# HPCC_Connector_B.net
KiCad netlist of a schematic drawn in Altium Designer
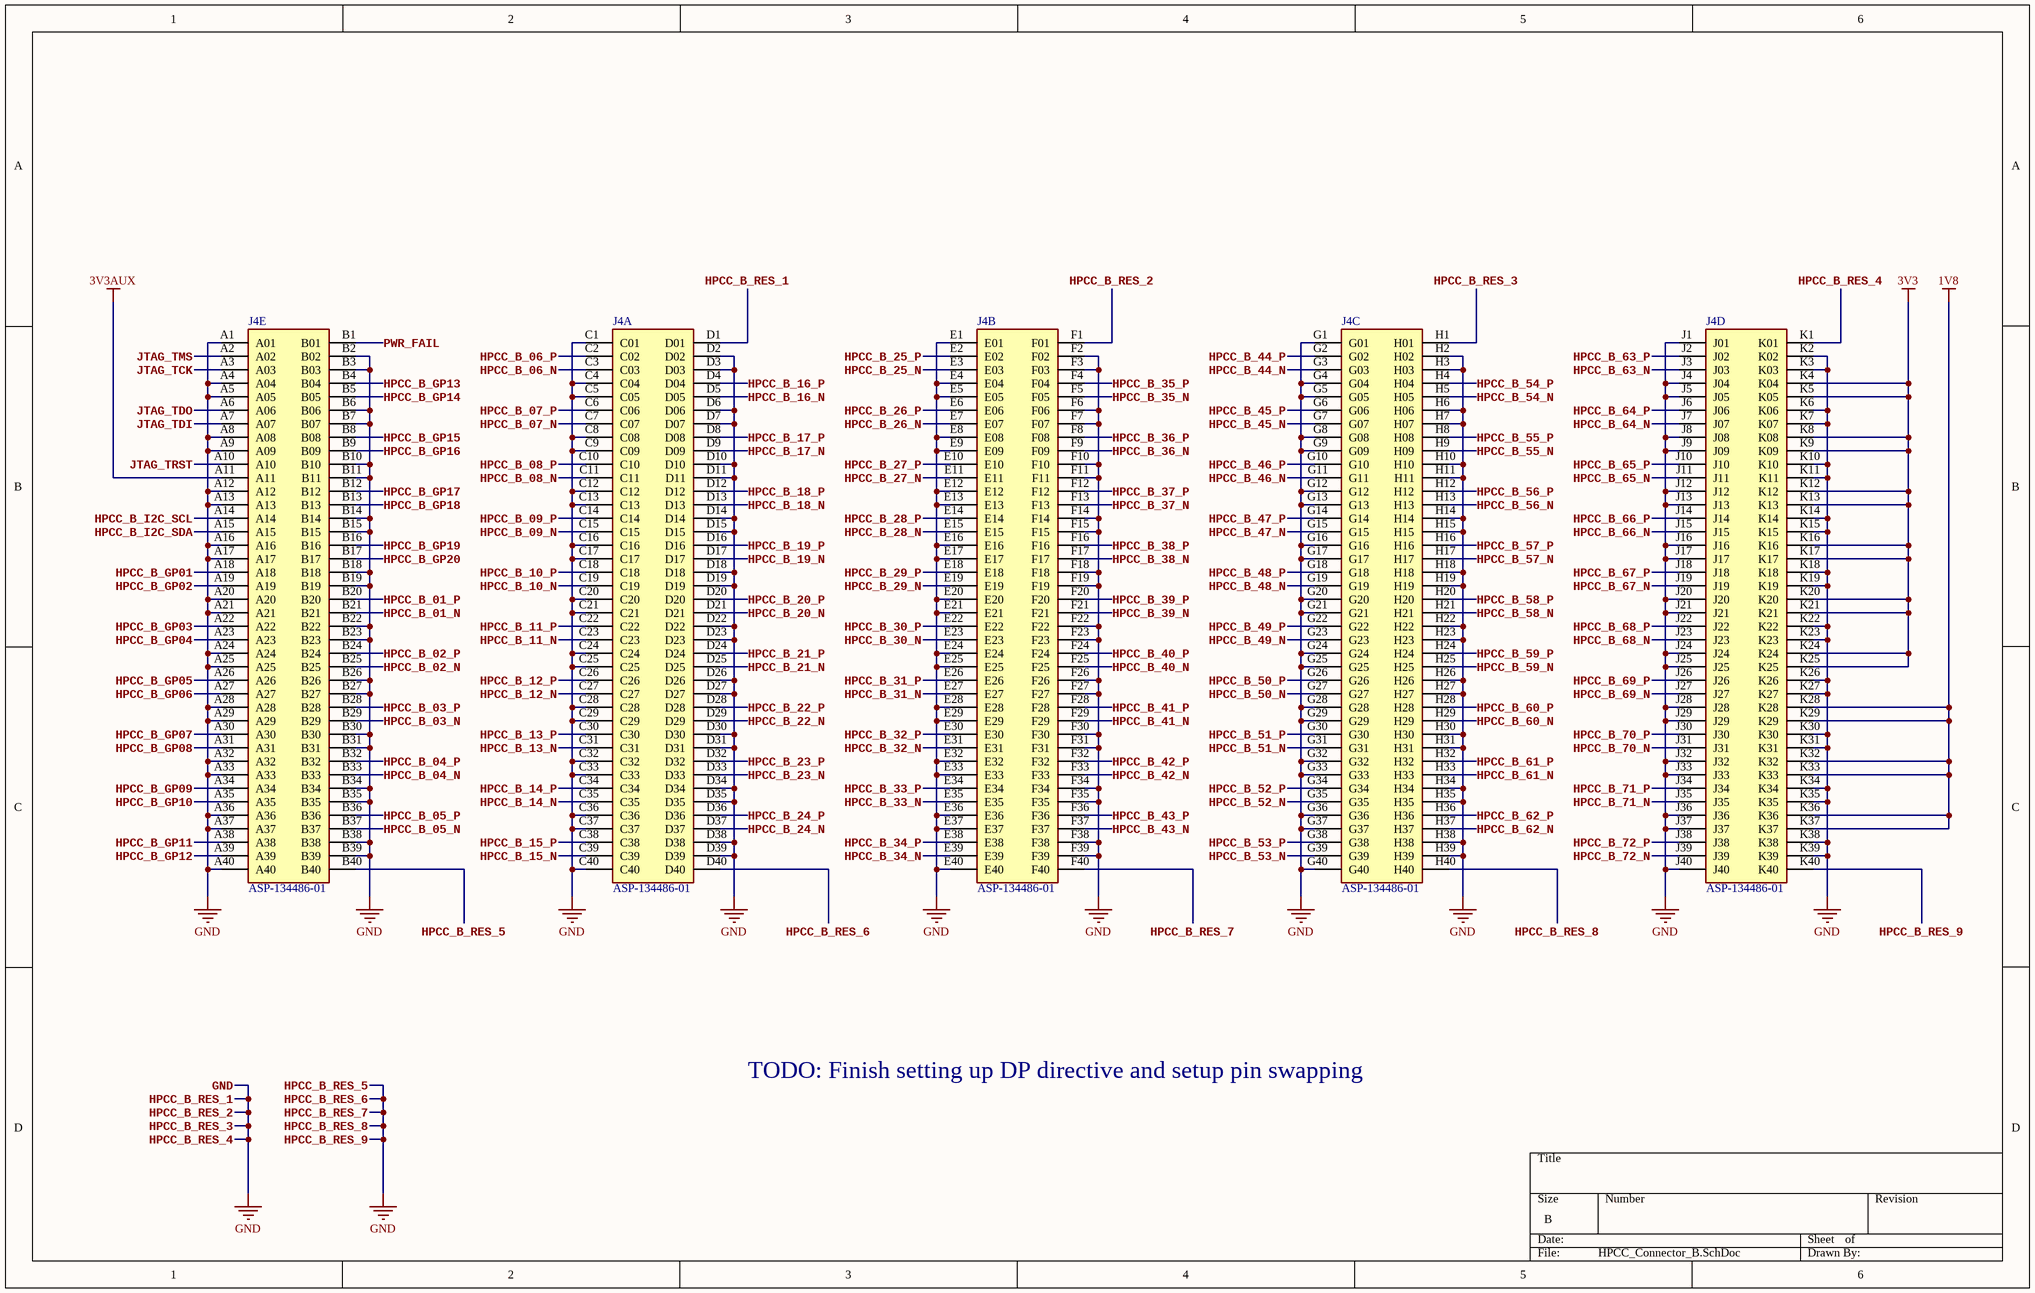
[diagram p0: HPCC_Connector_B.SchDoc]

(export (version "E")
  (design (tool "Eeschema 10.0.6"))
  (components
    (comp (ref "J4")
      (value "ASP-134486-01")
      (footprint "SAMTEC_ASP-134486-01")
      (description "400 Position Connector Array, Female Sockets Surface Mount Gold")
      (fields (field (name "MANUFACTURER") "Samtec"))
      (libsource (lib "Capstone_Schematic_Library") (part "ASP-134486-01"))
    )
  )
  (nets
    (net (code "1") (name "/HPCC_B_01_N") (class "Default")
      (node (ref "J4") (pin "B21") (pinfunction "B21_B21") (pintype "passive"))
    )
    (net (code "2") (name "/HPCC_B_01_P") (class "Default")
      (node (ref "J4") (pin "B20") (pinfunction "B20_B20") (pintype "passive"))
    )
    (net (code "3") (name "/HPCC_B_02_N") (class "Default")
      (node (ref "J4") (pin "B25") (pinfunction "B25_B25") (pintype "passive"))
    )
    (net (code "4") (name "/HPCC_B_02_P") (class "Default")
      (node (ref "J4") (pin "B24") (pinfunction "B24_B24") (pintype "passive"))
    )
    (net (code "5") (name "/HPCC_B_03_N") (class "Default")
      (node (ref "J4") (pin "B29") (pinfunction "B29_B29") (pintype "passive"))
    )
    (net (code "6") (name "/HPCC_B_03_P") (class "Default")
      (node (ref "J4") (pin "B28") (pinfunction "B28_B28") (pintype "passive"))
    )
    (net (code "7") (name "/HPCC_B_04_N") (class "Default")
      (node (ref "J4") (pin "B33") (pinfunction "B33_B33") (pintype "passive"))
    )
    (net (code "8") (name "/HPCC_B_04_P") (class "Default")
      (node (ref "J4") (pin "B32") (pinfunction "B32_B32") (pintype "passive"))
    )
    (net (code "9") (name "/HPCC_B_05_N") (class "Default")
      (node (ref "J4") (pin "B37") (pinfunction "B37_B37") (pintype "passive"))
    )
    (net (code "10") (name "/HPCC_B_05_P") (class "Default")
      (node (ref "J4") (pin "B36") (pinfunction "B36_B36") (pintype "passive"))
    )
    (net (code "11") (name "/HPCC_B_06_N") (class "Default")
      (node (ref "J4") (pin "C3") (pinfunction "C03_C3") (pintype "passive"))
    )
    (net (code "12") (name "/HPCC_B_06_P") (class "Default")
      (node (ref "J4") (pin "C2") (pinfunction "C02_C2") (pintype "passive"))
    )
    (net (code "13") (name "/HPCC_B_07_N") (class "Default")
      (node (ref "J4") (pin "C7") (pinfunction "C07_C7") (pintype "passive"))
    )
    (net (code "14") (name "/HPCC_B_07_P") (class "Default")
      (node (ref "J4") (pin "C6") (pinfunction "C06_C6") (pintype "passive"))
    )
    (net (code "15") (name "/HPCC_B_08_N") (class "Default")
      (node (ref "J4") (pin "C11") (pinfunction "C11_C11") (pintype "passive"))
    )
    (net (code "16") (name "/HPCC_B_08_P") (class "Default")
      (node (ref "J4") (pin "C10") (pinfunction "C10_C10") (pintype "passive"))
    )
    (net (code "17") (name "/HPCC_B_09_N") (class "Default")
      (node (ref "J4") (pin "C15") (pinfunction "C15_C15") (pintype "passive"))
    )
    (net (code "18") (name "/HPCC_B_09_P") (class "Default")
      (node (ref "J4") (pin "C14") (pinfunction "C14_C14") (pintype "passive"))
    )
    (net (code "19") (name "/HPCC_B_10_N") (class "Default")
      (node (ref "J4") (pin "C19") (pinfunction "C19_C19") (pintype "passive"))
    )
    (net (code "20") (name "/HPCC_B_10_P") (class "Default")
      (node (ref "J4") (pin "C18") (pinfunction "C18_C18") (pintype "passive"))
    )
    (net (code "21") (name "/HPCC_B_11_N") (class "Default")
      (node (ref "J4") (pin "C23") (pinfunction "C23_C23") (pintype "passive"))
    )
    (net (code "22") (name "/HPCC_B_11_P") (class "Default")
      (node (ref "J4") (pin "C22") (pinfunction "C22_C22") (pintype "passive"))
    )
    (net (code "23") (name "/HPCC_B_12_N") (class "Default")
      (node (ref "J4") (pin "C27") (pinfunction "C27_C27") (pintype "passive"))
    )
    (net (code "24") (name "/HPCC_B_12_P") (class "Default")
      (node (ref "J4") (pin "C26") (pinfunction "C26_C26") (pintype "passive"))
    )
    (net (code "25") (name "/HPCC_B_13_N") (class "Default")
      (node (ref "J4") (pin "C31") (pinfunction "C31_C31") (pintype "passive"))
    )
    (net (code "26") (name "/HPCC_B_13_P") (class "Default")
      (node (ref "J4") (pin "C30") (pinfunction "C30_C30") (pintype "passive"))
    )
    (net (code "27") (name "/HPCC_B_14_N") (class "Default")
      (node (ref "J4") (pin "C35") (pinfunction "C35_C35") (pintype "passive"))
    )
    (net (code "28") (name "/HPCC_B_14_P") (class "Default")
      (node (ref "J4") (pin "C34") (pinfunction "C34_C34") (pintype "passive"))
    )
    (net (code "29") (name "/HPCC_B_15_N") (class "Default")
      (node (ref "J4") (pin "C39") (pinfunction "C39_C39") (pintype "passive"))
    )
    (net (code "30") (name "/HPCC_B_15_P") (class "Default")
      (node (ref "J4") (pin "C38") (pinfunction "C38_C38") (pintype "passive"))
    )
    (net (code "31") (name "/HPCC_B_16_N") (class "Default")
      (node (ref "J4") (pin "D5") (pinfunction "D05_D5") (pintype "passive"))
    )
    (net (code "32") (name "/HPCC_B_16_P") (class "Default")
      (node (ref "J4") (pin "D4") (pinfunction "D04_D4") (pintype "passive"))
    )
    (net (code "33") (name "/HPCC_B_17_N") (class "Default")
      (node (ref "J4") (pin "D9") (pinfunction "D09_D9") (pintype "passive"))
    )
    (net (code "34") (name "/HPCC_B_17_P") (class "Default")
      (node (ref "J4") (pin "D8") (pinfunction "D08_D8") (pintype "passive"))
    )
    (net (code "35") (name "/HPCC_B_18_N") (class "Default")
      (node (ref "J4") (pin "D13") (pinfunction "D13_D13") (pintype "passive"))
    )
    (net (code "36") (name "/HPCC_B_18_P") (class "Default")
      (node (ref "J4") (pin "D12") (pinfunction "D12_D12") (pintype "passive"))
    )
    (net (code "37") (name "/HPCC_B_19_N") (class "Default")
      (node (ref "J4") (pin "D17") (pinfunction "D17_D17") (pintype "passive"))
    )
    (net (code "38") (name "/HPCC_B_19_P") (class "Default")
      (node (ref "J4") (pin "D16") (pinfunction "D16_D16") (pintype "passive"))
    )
    (net (code "39") (name "/HPCC_B_20_N") (class "Default")
      (node (ref "J4") (pin "D21") (pinfunction "D21_D21") (pintype "passive"))
    )
    (net (code "40") (name "/HPCC_B_20_P") (class "Default")
      (node (ref "J4") (pin "D20") (pinfunction "D20_D20") (pintype "passive"))
    )
    (net (code "41") (name "/HPCC_B_21_N") (class "Default")
      (node (ref "J4") (pin "D25") (pinfunction "D25_D25") (pintype "passive"))
    )
    (net (code "42") (name "/HPCC_B_21_P") (class "Default")
      (node (ref "J4") (pin "D24") (pinfunction "D24_D24") (pintype "passive"))
    )
    (net (code "43") (name "/HPCC_B_22_N") (class "Default")
      (node (ref "J4") (pin "D29") (pinfunction "D29_D29") (pintype "passive"))
    )
    (net (code "44") (name "/HPCC_B_22_P") (class "Default")
      (node (ref "J4") (pin "D28") (pinfunction "D28_D28") (pintype "passive"))
    )
    (net (code "45") (name "/HPCC_B_23_N") (class "Default")
      (node (ref "J4") (pin "D33") (pinfunction "D33_D33") (pintype "passive"))
    )
    (net (code "46") (name "/HPCC_B_23_P") (class "Default")
      (node (ref "J4") (pin "D32") (pinfunction "D32_D32") (pintype "passive"))
    )
    (net (code "47") (name "/HPCC_B_24_N") (class "Default")
      (node (ref "J4") (pin "D37") (pinfunction "D37_D37") (pintype "passive"))
    )
    (net (code "48") (name "/HPCC_B_24_P") (class "Default")
      (node (ref "J4") (pin "D36") (pinfunction "D36_D36") (pintype "passive"))
    )
    (net (code "49") (name "/HPCC_B_25_N") (class "Default")
      (node (ref "J4") (pin "E3") (pinfunction "E03_E3") (pintype "passive"))
    )
    (net (code "50") (name "/HPCC_B_25_P") (class "Default")
      (node (ref "J4") (pin "E2") (pinfunction "E02_E2") (pintype "passive"))
    )
    (net (code "51") (name "/HPCC_B_26_N") (class "Default")
      (node (ref "J4") (pin "E7") (pinfunction "E07_E7") (pintype "passive"))
    )
    (net (code "52") (name "/HPCC_B_26_P") (class "Default")
      (node (ref "J4") (pin "E6") (pinfunction "E06_E6") (pintype "passive"))
    )
    (net (code "53") (name "/HPCC_B_27_N") (class "Default")
      (node (ref "J4") (pin "E11") (pinfunction "E11_E11") (pintype "passive"))
    )
    (net (code "54") (name "/HPCC_B_27_P") (class "Default")
      (node (ref "J4") (pin "E10") (pinfunction "E10_E10") (pintype "passive"))
    )
    (net (code "55") (name "/HPCC_B_28_N") (class "Default")
      (node (ref "J4") (pin "E15") (pinfunction "E15_E15") (pintype "passive"))
    )
    (net (code "56") (name "/HPCC_B_28_P") (class "Default")
      (node (ref "J4") (pin "E14") (pinfunction "E14_E14") (pintype "passive"))
    )
    (net (code "57") (name "/HPCC_B_29_N") (class "Default")
      (node (ref "J4") (pin "E19") (pinfunction "E19_E19") (pintype "passive"))
    )
    (net (code "58") (name "/HPCC_B_29_P") (class "Default")
      (node (ref "J4") (pin "E18") (pinfunction "E18_E18") (pintype "passive"))
    )
    (net (code "59") (name "/HPCC_B_30_N") (class "Default")
      (node (ref "J4") (pin "E23") (pinfunction "E23_E23") (pintype "passive"))
    )
    (net (code "60") (name "/HPCC_B_30_P") (class "Default")
      (node (ref "J4") (pin "E22") (pinfunction "E22_E22") (pintype "passive"))
    )
    (net (code "61") (name "/HPCC_B_31_N") (class "Default")
      (node (ref "J4") (pin "E27") (pinfunction "E27_E27") (pintype "passive"))
    )
    (net (code "62") (name "/HPCC_B_31_P") (class "Default")
      (node (ref "J4") (pin "E26") (pinfunction "E26_E26") (pintype "passive"))
    )
    (net (code "63") (name "/HPCC_B_32_N") (class "Default")
      (node (ref "J4") (pin "E31") (pinfunction "E31_E31") (pintype "passive"))
    )
    (net (code "64") (name "/HPCC_B_32_P") (class "Default")
      (node (ref "J4") (pin "E30") (pinfunction "E30_E30") (pintype "passive"))
    )
    (net (code "65") (name "/HPCC_B_33_N") (class "Default")
      (node (ref "J4") (pin "E35") (pinfunction "E35_E35") (pintype "passive"))
    )
    (net (code "66") (name "/HPCC_B_33_P") (class "Default")
      (node (ref "J4") (pin "E34") (pinfunction "E34_E34") (pintype "passive"))
    )
    (net (code "67") (name "/HPCC_B_34_N") (class "Default")
      (node (ref "J4") (pin "E39") (pinfunction "E39_E39") (pintype "passive"))
    )
    (net (code "68") (name "/HPCC_B_34_P") (class "Default")
      (node (ref "J4") (pin "E38") (pinfunction "E38_E38") (pintype "passive"))
    )
    (net (code "69") (name "/HPCC_B_35_N") (class "Default")
      (node (ref "J4") (pin "F5") (pinfunction "F05_F5") (pintype "passive"))
    )
    (net (code "70") (name "/HPCC_B_35_P") (class "Default")
      (node (ref "J4") (pin "F4") (pinfunction "F04_F4") (pintype "passive"))
    )
    (net (code "71") (name "/HPCC_B_36_N") (class "Default")
      (node (ref "J4") (pin "F9") (pinfunction "F09_F9") (pintype "passive"))
    )
    (net (code "72") (name "/HPCC_B_36_P") (class "Default")
      (node (ref "J4") (pin "F8") (pinfunction "F08_F8") (pintype "passive"))
    )
    (net (code "73") (name "/HPCC_B_37_N") (class "Default")
      (node (ref "J4") (pin "F13") (pinfunction "F13_F13") (pintype "passive"))
    )
    (net (code "74") (name "/HPCC_B_37_P") (class "Default")
      (node (ref "J4") (pin "F12") (pinfunction "F12_F12") (pintype "passive"))
    )
    (net (code "75") (name "/HPCC_B_38_N") (class "Default")
      (node (ref "J4") (pin "F17") (pinfunction "F17_F17") (pintype "passive"))
    )
    (net (code "76") (name "/HPCC_B_38_P") (class "Default")
      (node (ref "J4") (pin "F16") (pinfunction "F16_F16") (pintype "passive"))
    )
    (net (code "77") (name "/HPCC_B_39_N") (class "Default")
      (node (ref "J4") (pin "F21") (pinfunction "F21_F21") (pintype "passive"))
    )
    (net (code "78") (name "/HPCC_B_39_P") (class "Default")
      (node (ref "J4") (pin "F20") (pinfunction "F20_F20") (pintype "passive"))
    )
    (net (code "79") (name "/HPCC_B_40_N") (class "Default")
      (node (ref "J4") (pin "F25") (pinfunction "F25_F25") (pintype "passive"))
    )
    (net (code "80") (name "/HPCC_B_40_P") (class "Default")
      (node (ref "J4") (pin "F24") (pinfunction "F24_F24") (pintype "passive"))
    )
    (net (code "81") (name "/HPCC_B_41_N") (class "Default")
      (node (ref "J4") (pin "F29") (pinfunction "F29_F29") (pintype "passive"))
    )
    (net (code "82") (name "/HPCC_B_41_P") (class "Default")
      (node (ref "J4") (pin "F28") (pinfunction "F28_F28") (pintype "passive"))
    )
    (net (code "83") (name "/HPCC_B_42_N") (class "Default")
      (node (ref "J4") (pin "F33") (pinfunction "F33_F33") (pintype "passive"))
    )
    (net (code "84") (name "/HPCC_B_42_P") (class "Default")
      (node (ref "J4") (pin "F32") (pinfunction "F32_F32") (pintype "passive"))
    )
    (net (code "85") (name "/HPCC_B_43_N") (class "Default")
      (node (ref "J4") (pin "F37") (pinfunction "F37_F37") (pintype "passive"))
    )
    (net (code "86") (name "/HPCC_B_43_P") (class "Default")
      (node (ref "J4") (pin "F36") (pinfunction "F36_F36") (pintype "passive"))
    )
    (net (code "87") (name "/HPCC_B_44_N") (class "Default")
      (node (ref "J4") (pin "G3") (pinfunction "G03_G3") (pintype "passive"))
    )
    (net (code "88") (name "/HPCC_B_44_P") (class "Default")
      (node (ref "J4") (pin "G2") (pinfunction "G02_G2") (pintype "passive"))
    )
    (net (code "89") (name "/HPCC_B_45_N") (class "Default")
      (node (ref "J4") (pin "G7") (pinfunction "G07_G7") (pintype "passive"))
    )
    (net (code "90") (name "/HPCC_B_45_P") (class "Default")
      (node (ref "J4") (pin "G6") (pinfunction "G06_G6") (pintype "passive"))
    )
    (net (code "91") (name "/HPCC_B_46_N") (class "Default")
      (node (ref "J4") (pin "G11") (pinfunction "G11_G11") (pintype "passive"))
    )
    (net (code "92") (name "/HPCC_B_46_P") (class "Default")
      (node (ref "J4") (pin "G10") (pinfunction "G10_G10") (pintype "passive"))
    )
    (net (code "93") (name "/HPCC_B_47_N") (class "Default")
      (node (ref "J4") (pin "G15") (pinfunction "G15_G15") (pintype "passive"))
    )
    (net (code "94") (name "/HPCC_B_47_P") (class "Default")
      (node (ref "J4") (pin "G14") (pinfunction "G14_G14") (pintype "passive"))
    )
    (net (code "95") (name "/HPCC_B_48_N") (class "Default")
      (node (ref "J4") (pin "G19") (pinfunction "G19_G19") (pintype "passive"))
    )
    (net (code "96") (name "/HPCC_B_48_P") (class "Default")
      (node (ref "J4") (pin "G18") (pinfunction "G18_G18") (pintype "passive"))
    )
    (net (code "97") (name "/HPCC_B_49_N") (class "Default")
      (node (ref "J4") (pin "G23") (pinfunction "G23_G23") (pintype "passive"))
    )
    (net (code "98") (name "/HPCC_B_49_P") (class "Default")
      (node (ref "J4") (pin "G22") (pinfunction "G22_G22") (pintype "passive"))
    )
    (net (code "99") (name "/HPCC_B_50_N") (class "Default")
      (node (ref "J4") (pin "G27") (pinfunction "G27_G27") (pintype "passive"))
    )
    (net (code "100") (name "/HPCC_B_50_P") (class "Default")
      (node (ref "J4") (pin "G26") (pinfunction "G26_G26") (pintype "passive"))
    )
    (net (code "101") (name "/HPCC_B_51_N") (class "Default")
      (node (ref "J4") (pin "G31") (pinfunction "G31_G31") (pintype "passive"))
    )
    (net (code "102") (name "/HPCC_B_51_P") (class "Default")
      (node (ref "J4") (pin "G30") (pinfunction "G30_G30") (pintype "passive"))
    )
    (net (code "103") (name "/HPCC_B_52_N") (class "Default")
      (node (ref "J4") (pin "G35") (pinfunction "G35_G35") (pintype "passive"))
    )
    (net (code "104") (name "/HPCC_B_52_P") (class "Default")
      (node (ref "J4") (pin "G34") (pinfunction "G34_G34") (pintype "passive"))
    )
    (net (code "105") (name "/HPCC_B_53_N") (class "Default")
      (node (ref "J4") (pin "G39") (pinfunction "G39_G39") (pintype "passive"))
    )
    (net (code "106") (name "/HPCC_B_53_P") (class "Default")
      (node (ref "J4") (pin "G38") (pinfunction "G38_G38") (pintype "passive"))
    )
    (net (code "107") (name "/HPCC_B_54_N") (class "Default")
      (node (ref "J4") (pin "H5") (pinfunction "H05_H5") (pintype "passive"))
    )
    (net (code "108") (name "/HPCC_B_54_P") (class "Default")
      (node (ref "J4") (pin "H4") (pinfunction "H04_H4") (pintype "passive"))
    )
    (net (code "109") (name "/HPCC_B_55_N") (class "Default")
      (node (ref "J4") (pin "H9") (pinfunction "H09_H9") (pintype "passive"))
    )
    (net (code "110") (name "/HPCC_B_55_P") (class "Default")
      (node (ref "J4") (pin "H8") (pinfunction "H08_H8") (pintype "passive"))
    )
    (net (code "111") (name "/HPCC_B_56_N") (class "Default")
      (node (ref "J4") (pin "H13") (pinfunction "H13_H13") (pintype "passive"))
    )
    (net (code "112") (name "/HPCC_B_56_P") (class "Default")
      (node (ref "J4") (pin "H12") (pinfunction "H12_H12") (pintype "passive"))
    )
    (net (code "113") (name "/HPCC_B_57_N") (class "Default")
      (node (ref "J4") (pin "H17") (pinfunction "H17_H17") (pintype "passive"))
    )
    (net (code "114") (name "/HPCC_B_57_P") (class "Default")
      (node (ref "J4") (pin "H16") (pinfunction "H16_H16") (pintype "passive"))
    )
    (net (code "115") (name "/HPCC_B_58_N") (class "Default")
      (node (ref "J4") (pin "H21") (pinfunction "H21_H21") (pintype "passive"))
    )
    (net (code "116") (name "/HPCC_B_58_P") (class "Default")
      (node (ref "J4") (pin "H20") (pinfunction "H20_H20") (pintype "passive"))
    )
    (net (code "117") (name "/HPCC_B_59_N") (class "Default")
      (node (ref "J4") (pin "H25") (pinfunction "H25_H25") (pintype "passive"))
    )
    (net (code "118") (name "/HPCC_B_59_P") (class "Default")
      (node (ref "J4") (pin "H24") (pinfunction "H24_H24") (pintype "passive"))
    )
    (net (code "119") (name "/HPCC_B_60_N") (class "Default")
      (node (ref "J4") (pin "H29") (pinfunction "H29_H29") (pintype "passive"))
    )
    (net (code "120") (name "/HPCC_B_60_P") (class "Default")
      (node (ref "J4") (pin "H28") (pinfunction "H28_H28") (pintype "passive"))
    )
    (net (code "121") (name "/HPCC_B_61_N") (class "Default")
      (node (ref "J4") (pin "H33") (pinfunction "H33_H33") (pintype "passive"))
    )
    (net (code "122") (name "/HPCC_B_61_P") (class "Default")
      (node (ref "J4") (pin "H32") (pinfunction "H32_H32") (pintype "passive"))
    )
    (net (code "123") (name "/HPCC_B_62_N") (class "Default")
      (node (ref "J4") (pin "H37") (pinfunction "H37_H37") (pintype "passive"))
    )
    (net (code "124") (name "/HPCC_B_62_P") (class "Default")
      (node (ref "J4") (pin "H36") (pinfunction "H36_H36") (pintype "passive"))
    )
    (net (code "125") (name "/HPCC_B_63_N") (class "Default")
      (node (ref "J4") (pin "J3") (pinfunction "J03_J3") (pintype "passive"))
    )
    (net (code "126") (name "/HPCC_B_63_P") (class "Default")
      (node (ref "J4") (pin "J2") (pinfunction "J02_J2") (pintype "passive"))
    )
    (net (code "127") (name "/HPCC_B_64_N") (class "Default")
      (node (ref "J4") (pin "J7") (pinfunction "J07_J7") (pintype "passive"))
    )
    (net (code "128") (name "/HPCC_B_64_P") (class "Default")
      (node (ref "J4") (pin "J6") (pinfunction "J06_J6") (pintype "passive"))
    )
    (net (code "129") (name "/HPCC_B_65_N") (class "Default")
      (node (ref "J4") (pin "J11") (pinfunction "J11_J11") (pintype "passive"))
    )
    (net (code "130") (name "/HPCC_B_65_P") (class "Default")
      (node (ref "J4") (pin "J10") (pinfunction "J10_J10") (pintype "passive"))
    )
    (net (code "131") (name "/HPCC_B_66_N") (class "Default")
      (node (ref "J4") (pin "J15") (pinfunction "J15_J15") (pintype "passive"))
    )
    (net (code "132") (name "/HPCC_B_66_P") (class "Default")
      (node (ref "J4") (pin "J14") (pinfunction "J14_J14") (pintype "passive"))
    )
    (net (code "133") (name "/HPCC_B_67_N") (class "Default")
      (node (ref "J4") (pin "J19") (pinfunction "J19_J19") (pintype "passive"))
    )
    (net (code "134") (name "/HPCC_B_67_P") (class "Default")
      (node (ref "J4") (pin "J18") (pinfunction "J18_J18") (pintype "passive"))
    )
    (net (code "135") (name "/HPCC_B_68_N") (class "Default")
      (node (ref "J4") (pin "J23") (pinfunction "J23_J23") (pintype "passive"))
    )
    (net (code "136") (name "/HPCC_B_68_P") (class "Default")
      (node (ref "J4") (pin "J22") (pinfunction "J22_J22") (pintype "passive"))
    )
    (net (code "137") (name "/HPCC_B_69_N") (class "Default")
      (node (ref "J4") (pin "J27") (pinfunction "J27_J27") (pintype "passive"))
    )
    (net (code "138") (name "/HPCC_B_69_P") (class "Default")
      (node (ref "J4") (pin "J26") (pinfunction "J26_J26") (pintype "passive"))
    )
    (net (code "139") (name "/HPCC_B_70_N") (class "Default")
      (node (ref "J4") (pin "J31") (pinfunction "J31_J31") (pintype "passive"))
    )
    (net (code "140") (name "/HPCC_B_70_P") (class "Default")
      (node (ref "J4") (pin "J30") (pinfunction "J30_J30") (pintype "passive"))
    )
    (net (code "141") (name "/HPCC_B_71_N") (class "Default")
      (node (ref "J4") (pin "J35") (pinfunction "J35_J35") (pintype "passive"))
    )
    (net (code "142") (name "/HPCC_B_71_P") (class "Default")
      (node (ref "J4") (pin "J34") (pinfunction "J34_J34") (pintype "passive"))
    )
    (net (code "143") (name "/HPCC_B_72_N") (class "Default")
      (node (ref "J4") (pin "J39") (pinfunction "J39_J39") (pintype "passive"))
    )
    (net (code "144") (name "/HPCC_B_72_P") (class "Default")
      (node (ref "J4") (pin "J38") (pinfunction "J38_J38") (pintype "passive"))
    )
    (net (code "145") (name "/HPCC_B_GP01") (class "Default")
      (node (ref "J4") (pin "A18") (pinfunction "A18_A18") (pintype "passive"))
    )
    (net (code "146") (name "/HPCC_B_GP02") (class "Default")
      (node (ref "J4") (pin "A19") (pinfunction "A19_A19") (pintype "passive"))
    )
    (net (code "147") (name "/HPCC_B_GP03") (class "Default")
      (node (ref "J4") (pin "A22") (pinfunction "A22_A22") (pintype "passive"))
    )
    (net (code "148") (name "/HPCC_B_GP04") (class "Default")
      (node (ref "J4") (pin "A23") (pinfunction "A23_A23") (pintype "passive"))
    )
    (net (code "149") (name "/HPCC_B_GP05") (class "Default")
      (node (ref "J4") (pin "A26") (pinfunction "A26_A26") (pintype "passive"))
    )
    (net (code "150") (name "/HPCC_B_GP06") (class "Default")
      (node (ref "J4") (pin "A27") (pinfunction "A27_A27") (pintype "passive"))
    )
    (net (code "151") (name "/HPCC_B_GP07") (class "Default")
      (node (ref "J4") (pin "A30") (pinfunction "A30_A30") (pintype "passive"))
    )
    (net (code "152") (name "/HPCC_B_GP08") (class "Default")
      (node (ref "J4") (pin "A31") (pinfunction "A31_A31") (pintype "passive"))
    )
    (net (code "153") (name "/HPCC_B_GP09") (class "Default")
      (node (ref "J4") (pin "A34") (pinfunction "A34_A34") (pintype "passive"))
    )
    (net (code "154") (name "/HPCC_B_GP10") (class "Default")
      (node (ref "J4") (pin "A35") (pinfunction "A35_A35") (pintype "passive"))
    )
    (net (code "155") (name "/HPCC_B_GP11") (class "Default")
      (node (ref "J4") (pin "A38") (pinfunction "A38_A38") (pintype "passive"))
    )
    (net (code "156") (name "/HPCC_B_GP12") (class "Default")
      (node (ref "J4") (pin "A39") (pinfunction "A39_A39") (pintype "passive"))
    )
    (net (code "157") (name "/HPCC_B_GP13") (class "Default")
      (node (ref "J4") (pin "B4") (pinfunction "B04_B4") (pintype "passive"))
    )
    (net (code "158") (name "/HPCC_B_GP14") (class "Default")
      (node (ref "J4") (pin "B5") (pinfunction "B05_B5") (pintype "passive"))
    )
    (net (code "159") (name "/HPCC_B_GP15") (class "Default")
      (node (ref "J4") (pin "B8") (pinfunction "B08_B8") (pintype "passive"))
    )
    (net (code "160") (name "/HPCC_B_GP16") (class "Default")
      (node (ref "J4") (pin "B9") (pinfunction "B09_B9") (pintype "passive"))
    )
    (net (code "161") (name "/HPCC_B_GP17") (class "Default")
      (node (ref "J4") (pin "B12") (pinfunction "B12_B12") (pintype "passive"))
    )
    (net (code "162") (name "/HPCC_B_GP18") (class "Default")
      (node (ref "J4") (pin "B13") (pinfunction "B13_B13") (pintype "passive"))
    )
    (net (code "163") (name "/HPCC_B_GP19") (class "Default")
      (node (ref "J4") (pin "B16") (pinfunction "B16_B16") (pintype "passive"))
    )
    (net (code "164") (name "/HPCC_B_GP20") (class "Default")
      (node (ref "J4") (pin "B17") (pinfunction "B17_B17") (pintype "passive"))
    )
    (net (code "165") (name "/HPCC_B_I2C_SCL") (class "Default")
      (node (ref "J4") (pin "A14") (pinfunction "A14_A14") (pintype "passive"))
    )
    (net (code "166") (name "/HPCC_B_I2C_SDA") (class "Default")
      (node (ref "J4") (pin "A15") (pinfunction "A15_A15") (pintype "passive"))
    )
    (net (code "167") (name "/JTAG_TCK") (class "Default")
      (node (ref "J4") (pin "A3") (pinfunction "A03_A3") (pintype "passive"))
    )
    (net (code "168") (name "/JTAG_TDI") (class "Default")
      (node (ref "J4") (pin "A7") (pinfunction "A07_A7") (pintype "passive"))
    )
    (net (code "169") (name "/JTAG_TDO") (class "Default")
      (node (ref "J4") (pin "A6") (pinfunction "A06_A6") (pintype "passive"))
    )
    (net (code "170") (name "/JTAG_TMS") (class "Default")
      (node (ref "J4") (pin "A2") (pinfunction "A02_A2") (pintype "passive"))
    )
    (net (code "171") (name "/JTAG_TRST") (class "Default")
      (node (ref "J4") (pin "A10") (pinfunction "A10_A10") (pintype "passive"))
    )
    (net (code "172") (name "/PWR_FAIL") (class "Default")
      (node (ref "J4") (pin "B1") (pinfunction "B01_B1") (pintype "passive"))
    )
    (net (code "173") (name "1V8") (class "Default")
      (node (ref "J4") (pin "K28") (pinfunction "K28_K28") (pintype "passive"))
      (node (ref "J4") (pin "K29") (pinfunction "K29_K29") (pintype "passive"))
      (node (ref "J4") (pin "K32") (pinfunction "K32_K32") (pintype "passive"))
      (node (ref "J4") (pin "K33") (pinfunction "K33_K33") (pintype "passive"))
      (node (ref "J4") (pin "K36") (pinfunction "K36_K36") (pintype "passive"))
      (node (ref "J4") (pin "K37") (pinfunction "K37_K37") (pintype "passive"))
    )
    (net (code "174") (name "3V3") (class "Default")
      (node (ref "J4") (pin "K12") (pinfunction "K12_K12") (pintype "passive"))
      (node (ref "J4") (pin "K13") (pinfunction "K13_K13") (pintype "passive"))
      (node (ref "J4") (pin "K16") (pinfunction "K16_K16") (pintype "passive"))
      (node (ref "J4") (pin "K17") (pinfunction "K17_K17") (pintype "passive"))
      (node (ref "J4") (pin "K20") (pinfunction "K20_K20") (pintype "passive"))
      (node (ref "J4") (pin "K21") (pinfunction "K21_K21") (pintype "passive"))
      (node (ref "J4") (pin "K24") (pinfunction "K24_K24") (pintype "passive"))
      (node (ref "J4") (pin "K25") (pinfunction "K25_K25") (pintype "passive"))
      (node (ref "J4") (pin "K4") (pinfunction "K04_K4") (pintype "passive"))
      (node (ref "J4") (pin "K5") (pinfunction "K05_K5") (pintype "passive"))
      (node (ref "J4") (pin "K8") (pinfunction "K08_K8") (pintype "passive"))
      (node (ref "J4") (pin "K9") (pinfunction "K09_K9") (pintype "passive"))
    )
    (net (code "175") (name "3V3AUX") (class "Default")
      (node (ref "J4") (pin "A11") (pinfunction "A11_A11") (pintype "passive"))
    )
    (net (code "176") (name "GND") (class "Default")
      (node (ref "J4") (pin "A1") (pinfunction "A01_A1") (pintype "passive"))
      (node (ref "J4") (pin "A12") (pinfunction "A12_A12") (pintype "passive"))
      (node (ref "J4") (pin "A13") (pinfunction "A13_A13") (pintype "passive"))
      (node (ref "J4") (pin "A16") (pinfunction "A16_A16") (pintype "passive"))
      (node (ref "J4") (pin "A17") (pinfunction "A17_A17") (pintype "passive"))
      (node (ref "J4") (pin "A20") (pinfunction "A20_A20") (pintype "passive"))
      (node (ref "J4") (pin "A21") (pinfunction "A21_A21") (pintype "passive"))
      (node (ref "J4") (pin "A24") (pinfunction "A24_A24") (pintype "passive"))
      (node (ref "J4") (pin "A25") (pinfunction "A25_A25") (pintype "passive"))
      (node (ref "J4") (pin "A28") (pinfunction "A28_A28") (pintype "passive"))
      (node (ref "J4") (pin "A29") (pinfunction "A29_A29") (pintype "passive"))
      (node (ref "J4") (pin "A32") (pinfunction "A32_A32") (pintype "passive"))
      (node (ref "J4") (pin "A33") (pinfunction "A33_A33") (pintype "passive"))
      (node (ref "J4") (pin "A36") (pinfunction "A36_A36") (pintype "passive"))
      (node (ref "J4") (pin "A37") (pinfunction "A37_A37") (pintype "passive"))
      (node (ref "J4") (pin "A4") (pinfunction "A04_A4") (pintype "passive"))
      (node (ref "J4") (pin "A40") (pinfunction "A40_A40") (pintype "passive"))
      (node (ref "J4") (pin "A5") (pinfunction "A05_A5") (pintype "passive"))
      (node (ref "J4") (pin "A8") (pinfunction "A08_A8") (pintype "passive"))
      (node (ref "J4") (pin "A9") (pinfunction "A09_A9") (pintype "passive"))
      (node (ref "J4") (pin "B10") (pinfunction "B10_B10") (pintype "passive"))
      (node (ref "J4") (pin "B11") (pinfunction "B11_B11") (pintype "passive"))
      (node (ref "J4") (pin "B14") (pinfunction "B14_B14") (pintype "passive"))
      (node (ref "J4") (pin "B15") (pinfunction "B15_B15") (pintype "passive"))
      (node (ref "J4") (pin "B18") (pinfunction "B18_B18") (pintype "passive"))
      (node (ref "J4") (pin "B19") (pinfunction "B19_B19") (pintype "passive"))
      (node (ref "J4") (pin "B2") (pinfunction "B02_B2") (pintype "passive"))
      (node (ref "J4") (pin "B22") (pinfunction "B22_B22") (pintype "passive"))
      (node (ref "J4") (pin "B23") (pinfunction "B23_B23") (pintype "passive"))
      (node (ref "J4") (pin "B26") (pinfunction "B26_B26") (pintype "passive"))
      (node (ref "J4") (pin "B27") (pinfunction "B27_B27") (pintype "passive"))
      (node (ref "J4") (pin "B3") (pinfunction "B03_B3") (pintype "passive"))
      (node (ref "J4") (pin "B30") (pinfunction "B30_B30") (pintype "passive"))
      (node (ref "J4") (pin "B31") (pinfunction "B31_B31") (pintype "passive"))
      (node (ref "J4") (pin "B34") (pinfunction "B34_B34") (pintype "passive"))
      (node (ref "J4") (pin "B35") (pinfunction "B35_B35") (pintype "passive"))
      (node (ref "J4") (pin "B38") (pinfunction "B38_B38") (pintype "passive"))
      (node (ref "J4") (pin "B39") (pinfunction "B39_B39") (pintype "passive"))
      (node (ref "J4") (pin "B40") (pinfunction "B40_B40") (pintype "passive"))
      (node (ref "J4") (pin "B6") (pinfunction "B06_B6") (pintype "passive"))
      (node (ref "J4") (pin "B7") (pinfunction "B07_B7") (pintype "passive"))
      (node (ref "J4") (pin "C1") (pinfunction "C01_C1") (pintype "passive"))
      (node (ref "J4") (pin "C12") (pinfunction "C12_C12") (pintype "passive"))
      (node (ref "J4") (pin "C13") (pinfunction "C13_C13") (pintype "passive"))
      (node (ref "J4") (pin "C16") (pinfunction "C16_C16") (pintype "passive"))
      (node (ref "J4") (pin "C17") (pinfunction "C17_C17") (pintype "passive"))
      (node (ref "J4") (pin "C20") (pinfunction "C20_C20") (pintype "passive"))
      (node (ref "J4") (pin "C21") (pinfunction "C21_C21") (pintype "passive"))
      (node (ref "J4") (pin "C24") (pinfunction "C24_C24") (pintype "passive"))
      (node (ref "J4") (pin "C25") (pinfunction "C25_C25") (pintype "passive"))
      (node (ref "J4") (pin "C28") (pinfunction "C28_C28") (pintype "passive"))
      (node (ref "J4") (pin "C29") (pinfunction "C29_C29") (pintype "passive"))
      (node (ref "J4") (pin "C32") (pinfunction "C32_C32") (pintype "passive"))
      (node (ref "J4") (pin "C33") (pinfunction "C33_C33") (pintype "passive"))
      (node (ref "J4") (pin "C36") (pinfunction "C36_C36") (pintype "passive"))
      (node (ref "J4") (pin "C37") (pinfunction "C37_C37") (pintype "passive"))
      (node (ref "J4") (pin "C4") (pinfunction "C04_C4") (pintype "passive"))
      (node (ref "J4") (pin "C40") (pinfunction "C40_C40") (pintype "passive"))
      (node (ref "J4") (pin "C5") (pinfunction "C05_C5") (pintype "passive"))
      (node (ref "J4") (pin "C8") (pinfunction "C08_C8") (pintype "passive"))
      (node (ref "J4") (pin "C9") (pinfunction "C09_C9") (pintype "passive"))
      (node (ref "J4") (pin "D1") (pinfunction "D01_D1") (pintype "passive"))
      (node (ref "J4") (pin "D10") (pinfunction "D10_D10") (pintype "passive"))
      (node (ref "J4") (pin "D11") (pinfunction "D11_D11") (pintype "passive"))
      (node (ref "J4") (pin "D14") (pinfunction "D14_D14") (pintype "passive"))
      (node (ref "J4") (pin "D15") (pinfunction "D15_D15") (pintype "passive"))
      (node (ref "J4") (pin "D18") (pinfunction "D18_D18") (pintype "passive"))
      (node (ref "J4") (pin "D19") (pinfunction "D19_D19") (pintype "passive"))
      (node (ref "J4") (pin "D2") (pinfunction "D02_D2") (pintype "passive"))
      (node (ref "J4") (pin "D22") (pinfunction "D22_D22") (pintype "passive"))
      (node (ref "J4") (pin "D23") (pinfunction "D23_D23") (pintype "passive"))
      (node (ref "J4") (pin "D26") (pinfunction "D26_D26") (pintype "passive"))
      (node (ref "J4") (pin "D27") (pinfunction "D27_D27") (pintype "passive"))
      (node (ref "J4") (pin "D3") (pinfunction "D03_D3") (pintype "passive"))
      (node (ref "J4") (pin "D30") (pinfunction "D30_D30") (pintype "passive"))
      (node (ref "J4") (pin "D31") (pinfunction "D31_D31") (pintype "passive"))
      (node (ref "J4") (pin "D34") (pinfunction "D34_D34") (pintype "passive"))
      (node (ref "J4") (pin "D35") (pinfunction "D35_D35") (pintype "passive"))
      (node (ref "J4") (pin "D38") (pinfunction "D38_D38") (pintype "passive"))
      (node (ref "J4") (pin "D39") (pinfunction "D39_D39") (pintype "passive"))
      (node (ref "J4") (pin "D40") (pinfunction "D40_D40") (pintype "passive"))
      (node (ref "J4") (pin "D6") (pinfunction "D06_D6") (pintype "passive"))
      (node (ref "J4") (pin "D7") (pinfunction "D07_D7") (pintype "passive"))
      (node (ref "J4") (pin "E1") (pinfunction "E01_E1") (pintype "passive"))
      (node (ref "J4") (pin "E12") (pinfunction "E12_E12") (pintype "passive"))
      (node (ref "J4") (pin "E13") (pinfunction "E13_E13") (pintype "passive"))
      (node (ref "J4") (pin "E16") (pinfunction "E16_E16") (pintype "passive"))
      (node (ref "J4") (pin "E17") (pinfunction "E17_E17") (pintype "passive"))
      (node (ref "J4") (pin "E20") (pinfunction "E20_E20") (pintype "passive"))
      (node (ref "J4") (pin "E21") (pinfunction "E21_E21") (pintype "passive"))
      (node (ref "J4") (pin "E24") (pinfunction "E24_E24") (pintype "passive"))
      (node (ref "J4") (pin "E25") (pinfunction "E25_E25") (pintype "passive"))
      (node (ref "J4") (pin "E28") (pinfunction "E28_E28") (pintype "passive"))
      (node (ref "J4") (pin "E29") (pinfunction "E29_E29") (pintype "passive"))
      (node (ref "J4") (pin "E32") (pinfunction "E32_E32") (pintype "passive"))
      (node (ref "J4") (pin "E33") (pinfunction "E33_E33") (pintype "passive"))
      (node (ref "J4") (pin "E36") (pinfunction "E36_E36") (pintype "passive"))
      (node (ref "J4") (pin "E37") (pinfunction "E37_E37") (pintype "passive"))
      (node (ref "J4") (pin "E4") (pinfunction "E04_E4") (pintype "passive"))
      (node (ref "J4") (pin "E40") (pinfunction "E40_E40") (pintype "passive"))
      (node (ref "J4") (pin "E5") (pinfunction "E05_E5") (pintype "passive"))
      (node (ref "J4") (pin "E8") (pinfunction "E08_E8") (pintype "passive"))
      (node (ref "J4") (pin "E9") (pinfunction "E09_E9") (pintype "passive"))
      (node (ref "J4") (pin "F1") (pinfunction "F01_F1") (pintype "passive"))
      (node (ref "J4") (pin "F10") (pinfunction "F10_F10") (pintype "passive"))
      (node (ref "J4") (pin "F11") (pinfunction "F11_F11") (pintype "passive"))
      (node (ref "J4") (pin "F14") (pinfunction "F14_F14") (pintype "passive"))
      (node (ref "J4") (pin "F15") (pinfunction "F15_F15") (pintype "passive"))
      (node (ref "J4") (pin "F18") (pinfunction "F18_F18") (pintype "passive"))
      (node (ref "J4") (pin "F19") (pinfunction "F19_F19") (pintype "passive"))
      (node (ref "J4") (pin "F2") (pinfunction "F02_F2") (pintype "passive"))
      (node (ref "J4") (pin "F22") (pinfunction "F22_F22") (pintype "passive"))
      (node (ref "J4") (pin "F23") (pinfunction "F23_F23") (pintype "passive"))
      (node (ref "J4") (pin "F26") (pinfunction "F26_F26") (pintype "passive"))
      (node (ref "J4") (pin "F27") (pinfunction "F27_F27") (pintype "passive"))
      (node (ref "J4") (pin "F3") (pinfunction "F03_F3") (pintype "passive"))
      (node (ref "J4") (pin "F30") (pinfunction "F30_F30") (pintype "passive"))
      (node (ref "J4") (pin "F31") (pinfunction "F31_F31") (pintype "passive"))
      (node (ref "J4") (pin "F34") (pinfunction "F34_F34") (pintype "passive"))
      (node (ref "J4") (pin "F35") (pinfunction "F35_F35") (pintype "passive"))
      (node (ref "J4") (pin "F38") (pinfunction "F38_F38") (pintype "passive"))
      (node (ref "J4") (pin "F39") (pinfunction "F39_F39") (pintype "passive"))
      (node (ref "J4") (pin "F40") (pinfunction "F40_F40") (pintype "passive"))
      (node (ref "J4") (pin "F6") (pinfunction "F06_F6") (pintype "passive"))
      (node (ref "J4") (pin "F7") (pinfunction "F07_F7") (pintype "passive"))
      (node (ref "J4") (pin "G1") (pinfunction "G01_G1") (pintype "passive"))
      (node (ref "J4") (pin "G12") (pinfunction "G12_G12") (pintype "passive"))
      (node (ref "J4") (pin "G13") (pinfunction "G13_G13") (pintype "passive"))
      (node (ref "J4") (pin "G16") (pinfunction "G16_G16") (pintype "passive"))
      (node (ref "J4") (pin "G17") (pinfunction "G17_G17") (pintype "passive"))
      (node (ref "J4") (pin "G20") (pinfunction "G20_G20") (pintype "passive"))
      (node (ref "J4") (pin "G21") (pinfunction "G21_G21") (pintype "passive"))
      (node (ref "J4") (pin "G24") (pinfunction "G24_G24") (pintype "passive"))
      (node (ref "J4") (pin "G25") (pinfunction "G25_G25") (pintype "passive"))
      (node (ref "J4") (pin "G28") (pinfunction "G28_G28") (pintype "passive"))
      (node (ref "J4") (pin "G29") (pinfunction "G29_G29") (pintype "passive"))
      (node (ref "J4") (pin "G32") (pinfunction "G32_G32") (pintype "passive"))
      (node (ref "J4") (pin "G33") (pinfunction "G33_G33") (pintype "passive"))
      (node (ref "J4") (pin "G36") (pinfunction "G36_G36") (pintype "passive"))
      (node (ref "J4") (pin "G37") (pinfunction "G37_G37") (pintype "passive"))
      (node (ref "J4") (pin "G4") (pinfunction "G04_G4") (pintype "passive"))
      (node (ref "J4") (pin "G40") (pinfunction "G40_G40") (pintype "passive"))
      (node (ref "J4") (pin "G5") (pinfunction "G05_G5") (pintype "passive"))
      (node (ref "J4") (pin "G8") (pinfunction "G08_G8") (pintype "passive"))
      (node (ref "J4") (pin "G9") (pinfunction "G09_G9") (pintype "passive"))
      (node (ref "J4") (pin "H1") (pinfunction "H01_H1") (pintype "passive"))
      (node (ref "J4") (pin "H10") (pinfunction "H10_H10") (pintype "passive"))
      (node (ref "J4") (pin "H11") (pinfunction "H11_H11") (pintype "passive"))
      (node (ref "J4") (pin "H14") (pinfunction "H14_H14") (pintype "passive"))
      (node (ref "J4") (pin "H15") (pinfunction "H15_H15") (pintype "passive"))
      (node (ref "J4") (pin "H18") (pinfunction "H18_H18") (pintype "passive"))
      (node (ref "J4") (pin "H19") (pinfunction "H19_H19") (pintype "passive"))
      (node (ref "J4") (pin "H2") (pinfunction "H02_H2") (pintype "passive"))
      (node (ref "J4") (pin "H22") (pinfunction "H22_H22") (pintype "passive"))
      (node (ref "J4") (pin "H23") (pinfunction "H23_H23") (pintype "passive"))
      (node (ref "J4") (pin "H26") (pinfunction "H26_H26") (pintype "passive"))
      (node (ref "J4") (pin "H27") (pinfunction "H27_H27") (pintype "passive"))
      (node (ref "J4") (pin "H3") (pinfunction "H03_H3") (pintype "passive"))
      (node (ref "J4") (pin "H30") (pinfunction "H30_H30") (pintype "passive"))
      (node (ref "J4") (pin "H31") (pinfunction "H31_H31") (pintype "passive"))
      (node (ref "J4") (pin "H34") (pinfunction "H34_H34") (pintype "passive"))
      (node (ref "J4") (pin "H35") (pinfunction "H35_H35") (pintype "passive"))
      (node (ref "J4") (pin "H38") (pinfunction "H38_H38") (pintype "passive"))
      (node (ref "J4") (pin "H39") (pinfunction "H39_H39") (pintype "passive"))
      (node (ref "J4") (pin "H40") (pinfunction "H40_H40") (pintype "passive"))
      (node (ref "J4") (pin "H6") (pinfunction "H06_H6") (pintype "passive"))
      (node (ref "J4") (pin "H7") (pinfunction "H07_H7") (pintype "passive"))
      (node (ref "J4") (pin "J1") (pinfunction "J01_J1") (pintype "passive"))
      (node (ref "J4") (pin "J12") (pinfunction "J12_J12") (pintype "passive"))
      (node (ref "J4") (pin "J13") (pinfunction "J13_J13") (pintype "passive"))
      (node (ref "J4") (pin "J16") (pinfunction "J16_J16") (pintype "passive"))
      (node (ref "J4") (pin "J17") (pinfunction "J17_J17") (pintype "passive"))
      (node (ref "J4") (pin "J20") (pinfunction "J20_J20") (pintype "passive"))
      (node (ref "J4") (pin "J21") (pinfunction "J21_J21") (pintype "passive"))
      (node (ref "J4") (pin "J24") (pinfunction "J24_J24") (pintype "passive"))
      (node (ref "J4") (pin "J25") (pinfunction "J25_J25") (pintype "passive"))
      (node (ref "J4") (pin "J28") (pinfunction "J28_J28") (pintype "passive"))
      (node (ref "J4") (pin "J29") (pinfunction "J29_J29") (pintype "passive"))
      (node (ref "J4") (pin "J32") (pinfunction "J32_J32") (pintype "passive"))
      (node (ref "J4") (pin "J33") (pinfunction "J33_J33") (pintype "passive"))
      (node (ref "J4") (pin "J36") (pinfunction "J36_J36") (pintype "passive"))
      (node (ref "J4") (pin "J37") (pinfunction "J37_J37") (pintype "passive"))
      (node (ref "J4") (pin "J4") (pinfunction "J04_J4") (pintype "passive"))
      (node (ref "J4") (pin "J40") (pinfunction "J40_J40") (pintype "passive"))
      (node (ref "J4") (pin "J5") (pinfunction "J05_J5") (pintype "passive"))
      (node (ref "J4") (pin "J8") (pinfunction "J08_J8") (pintype "passive"))
      (node (ref "J4") (pin "J9") (pinfunction "J09_J9") (pintype "passive"))
      (node (ref "J4") (pin "K1") (pinfunction "K01_K1") (pintype "passive"))
      (node (ref "J4") (pin "K10") (pinfunction "K10_K10") (pintype "passive"))
      (node (ref "J4") (pin "K11") (pinfunction "K11_K11") (pintype "passive"))
      (node (ref "J4") (pin "K14") (pinfunction "K14_K14") (pintype "passive"))
      (node (ref "J4") (pin "K15") (pinfunction "K15_K15") (pintype "passive"))
      (node (ref "J4") (pin "K18") (pinfunction "K18_K18") (pintype "passive"))
      (node (ref "J4") (pin "K19") (pinfunction "K19_K19") (pintype "passive"))
      (node (ref "J4") (pin "K2") (pinfunction "K02_K2") (pintype "passive"))
      (node (ref "J4") (pin "K22") (pinfunction "K22_K22") (pintype "passive"))
      (node (ref "J4") (pin "K23") (pinfunction "K23_K23") (pintype "passive"))
      (node (ref "J4") (pin "K26") (pinfunction "K26_K26") (pintype "passive"))
      (node (ref "J4") (pin "K27") (pinfunction "K27_K27") (pintype "passive"))
      (node (ref "J4") (pin "K3") (pinfunction "K03_K3") (pintype "passive"))
      (node (ref "J4") (pin "K30") (pinfunction "K30_K30") (pintype "passive"))
      (node (ref "J4") (pin "K31") (pinfunction "K31_K31") (pintype "passive"))
      (node (ref "J4") (pin "K34") (pinfunction "K34_K34") (pintype "passive"))
      (node (ref "J4") (pin "K35") (pinfunction "K35_K35") (pintype "passive"))
      (node (ref "J4") (pin "K38") (pinfunction "K38_K38") (pintype "passive"))
      (node (ref "J4") (pin "K39") (pinfunction "K39_K39") (pintype "passive"))
      (node (ref "J4") (pin "K40") (pinfunction "K40_K40") (pintype "passive"))
      (node (ref "J4") (pin "K6") (pinfunction "K06_K6") (pintype "passive"))
      (node (ref "J4") (pin "K7") (pinfunction "K07_K7") (pintype "passive"))
    )
  )
)
